# 2__Microcontroller.net
KiCad netlist of a schematic drawn in Altium Designer
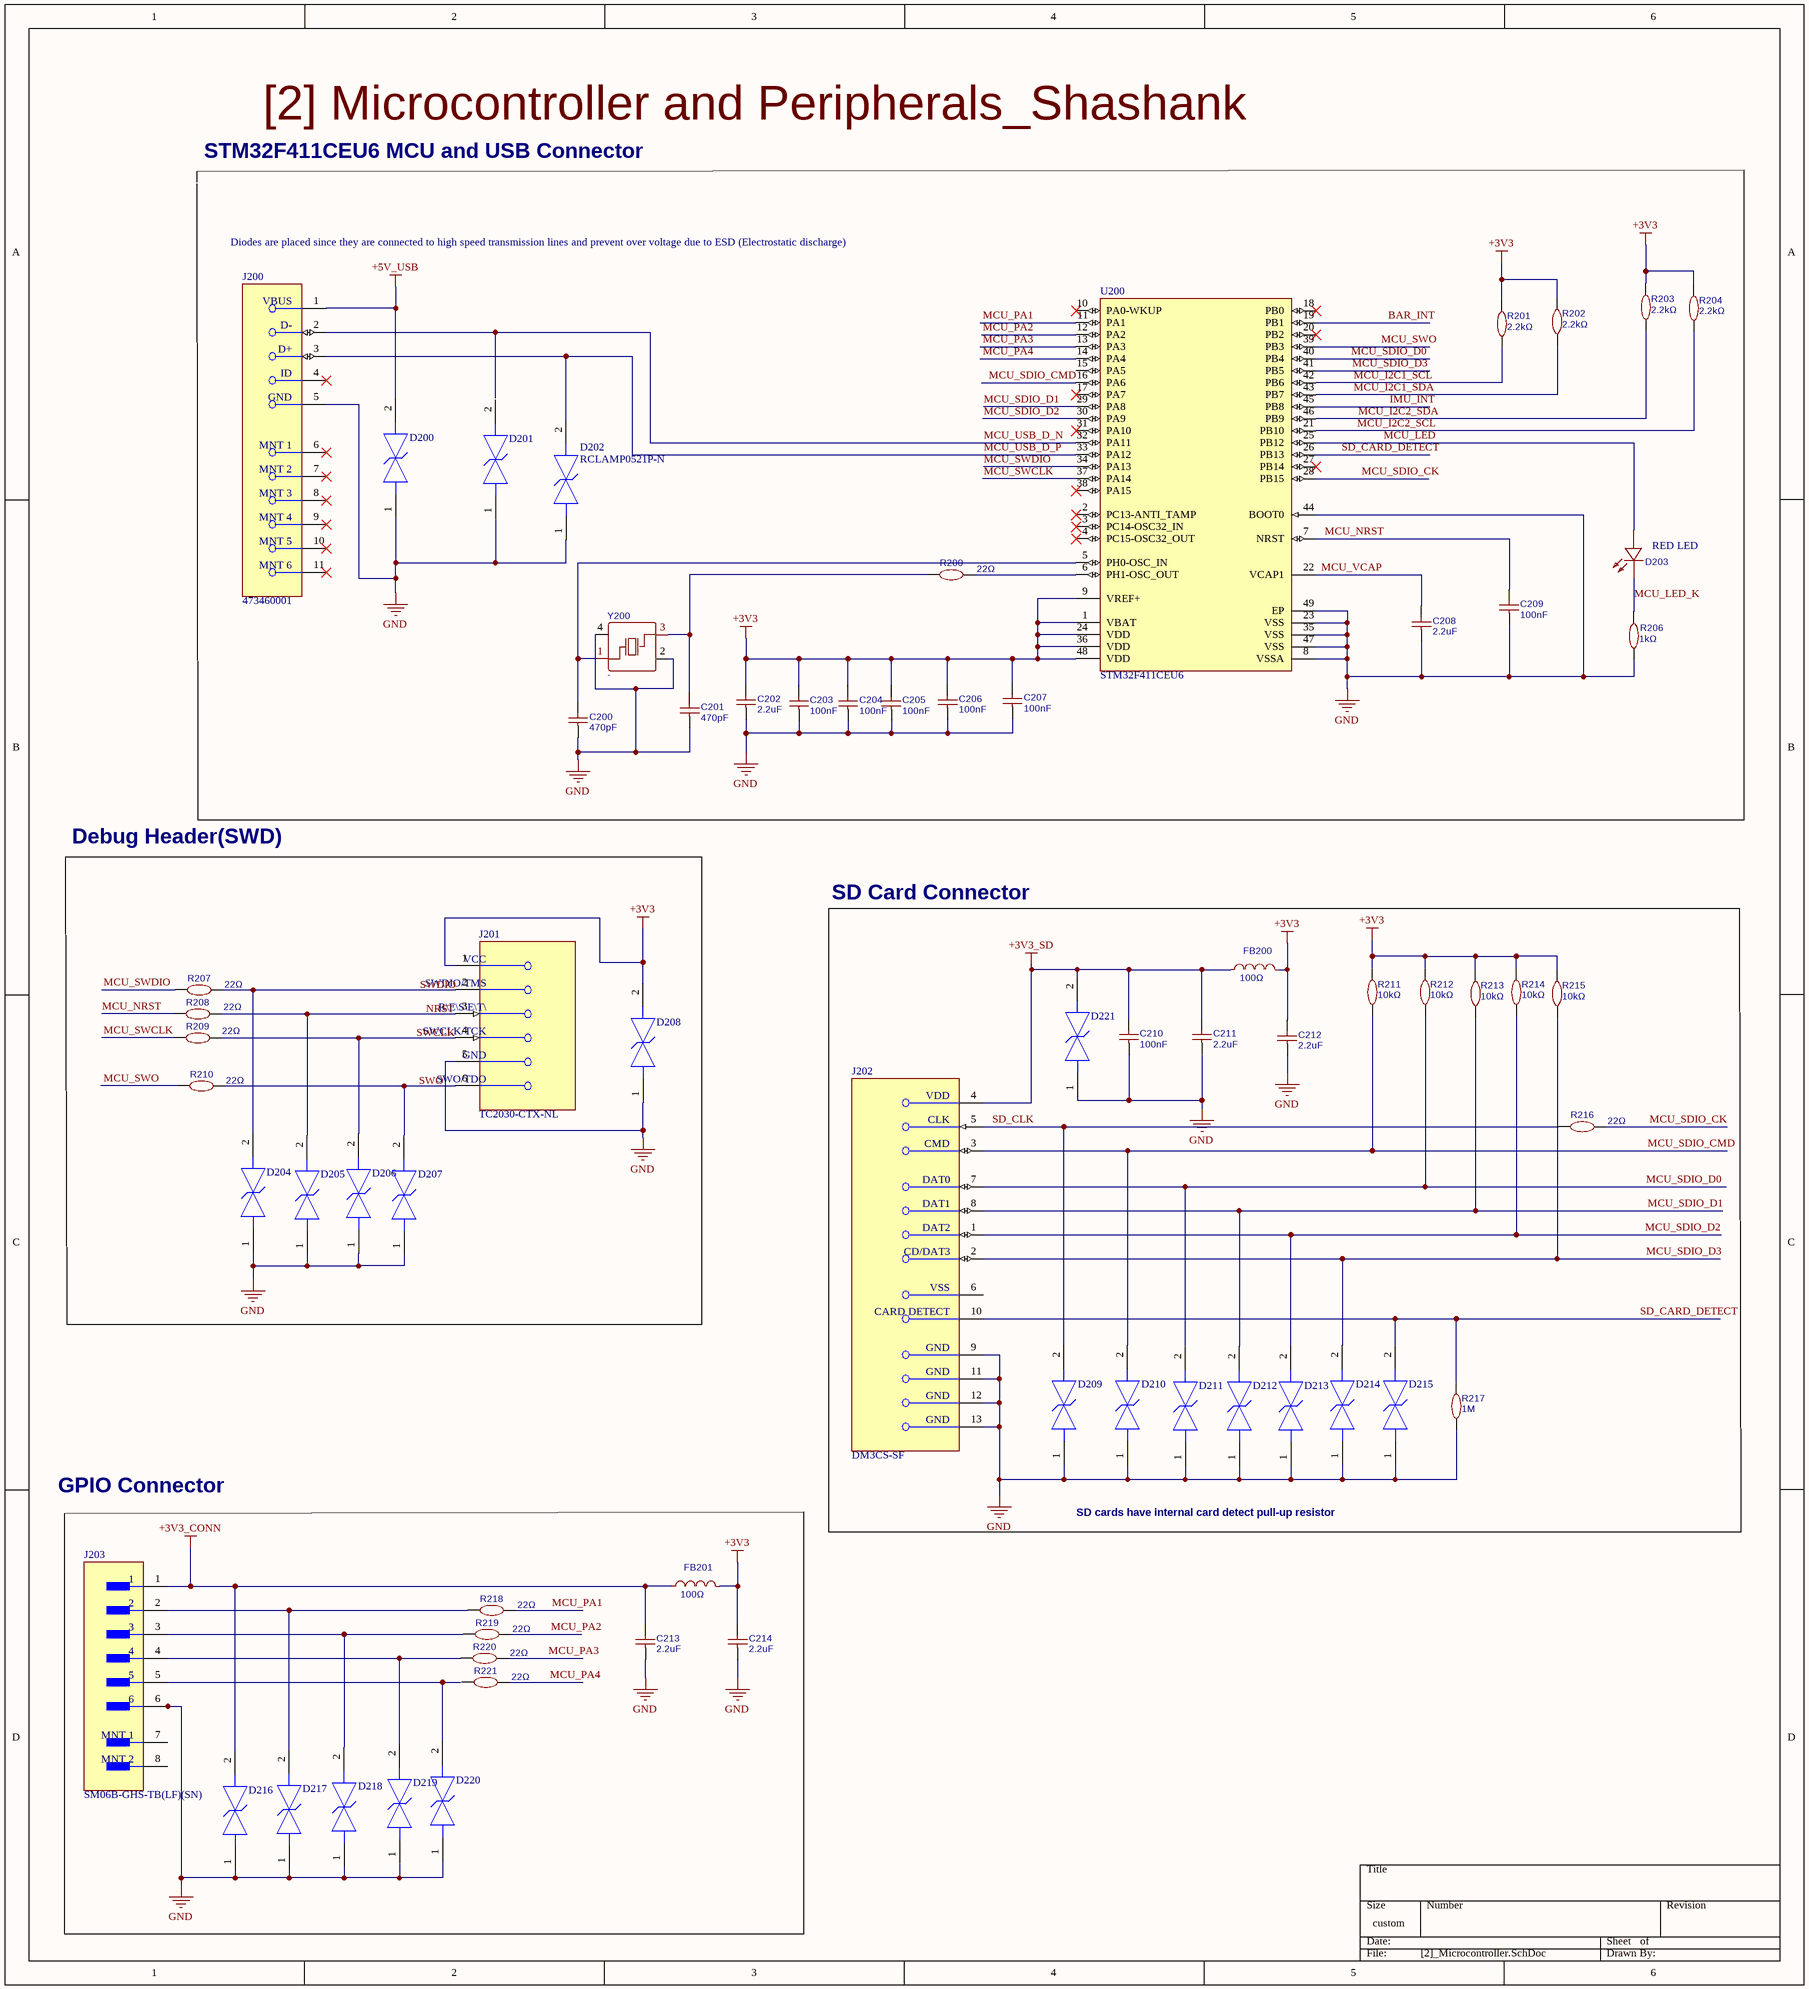
[diagram p0: [2]_Microcontroller.SchDoc]

(export (version "E")
  (design (tool "Eeschema 10.0.6"))
  (components
    (comp (ref "C200")
      (value "470pF")
      (footprint "C0402")
      (fields (field (name "MANUFACTURER") "FH(风华)") (field (name "MANUFACTURER PART") "0402B471K500NT"))
      (libsource (lib "Power_Lib") (part "470pF"))
    )
    (comp (ref "C201")
      (value "470pF")
      (footprint "C0402")
      (fields (field (name "MANUFACTURER") "FH(风华)") (field (name "MANUFACTURER PART") "0402B471K500NT"))
      (libsource (lib "Power_Lib") (part "470pF"))
    )
    (comp (ref "C202")
      (value "2.2uF")
      (footprint "C0603")
      (fields
        (field (name "MANUFACTURER PART") "CL10A225KO8NNNC")
        (field (name "MANUFACTURER") "SAMSUNG(三星)")
      )
      (libsource (lib "Power_Lib") (part "2.2uF"))
    )
    (comp (ref "C203")
      (value "100nF")
      (footprint "C0402")
      (fields (field (name "MANUFACTURER") "FH(风华)") (field (name "MANUFACTURER PART") "0402B471K500NT"))
      (libsource (lib "Power_Lib") (part "470pF"))
    )
    (comp (ref "C204")
      (value "100nF")
      (footprint "C0402")
      (fields (field (name "MANUFACTURER") "FH(风华)") (field (name "MANUFACTURER PART") "0402B471K500NT"))
      (libsource (lib "Power_Lib") (part "470pF"))
    )
    (comp (ref "C205")
      (value "100nF")
      (footprint "C0402")
      (fields (field (name "MANUFACTURER") "FH(风华)") (field (name "MANUFACTURER PART") "0402B471K500NT"))
      (libsource (lib "Power_Lib") (part "470pF"))
    )
    (comp (ref "C206")
      (value "100nF")
      (footprint "C0402")
      (fields (field (name "MANUFACTURER") "FH(风华)") (field (name "MANUFACTURER PART") "0402B471K500NT"))
      (libsource (lib "Power_Lib") (part "470pF"))
    )
    (comp (ref "C207")
      (value "100nF")
      (footprint "C0402")
      (fields (field (name "MANUFACTURER") "FH(风华)") (field (name "MANUFACTURER PART") "0402B471K500NT"))
      (libsource (lib "Power_Lib") (part "470pF"))
    )
    (comp (ref "C208")
      (value "2.2uF")
      (footprint "C0603")
      (fields
        (field (name "MANUFACTURER PART") "CL10A225KO8NNNC")
        (field (name "MANUFACTURER") "SAMSUNG(三星)")
      )
      (libsource (lib "Power_Lib") (part "2.2uF"))
    )
    (comp (ref "C209")
      (value "100nF")
      (footprint "C0402")
      (fields (field (name "MANUFACTURER") "FH(风华)") (field (name "MANUFACTURER PART") "0402B471K500NT"))
      (libsource (lib "Power_Lib") (part "470pF"))
    )
    (comp (ref "C210")
      (value "100nF")
      (footprint "C0402")
      (fields (field (name "MANUFACTURER") "FH(风华)") (field (name "MANUFACTURER PART") "0402B471K500NT"))
      (libsource (lib "Power_Lib") (part "470pF"))
    )
    (comp (ref "C211")
      (value "2.2uF")
      (footprint "C0603")
      (fields
        (field (name "MANUFACTURER PART") "CL10A225KO8NNNC")
        (field (name "MANUFACTURER") "SAMSUNG(三星)")
      )
      (libsource (lib "Power_Lib") (part "2.2uF"))
    )
    (comp (ref "C212")
      (value "2.2uF")
      (footprint "C0603")
      (fields
        (field (name "MANUFACTURER PART") "CL10A225KO8NNNC")
        (field (name "MANUFACTURER") "SAMSUNG(三星)")
      )
      (libsource (lib "Power_Lib") (part "2.2uF"))
    )
    (comp (ref "C213")
      (value "2.2uF")
      (footprint "C0603")
      (fields
        (field (name "MANUFACTURER PART") "CL10A225KO8NNNC")
        (field (name "MANUFACTURER") "SAMSUNG(三星)")
      )
      (libsource (lib "Power_Lib") (part "2.2uF"))
    )
    (comp (ref "C214")
      (value "2.2uF")
      (footprint "C0603")
      (fields
        (field (name "MANUFACTURER PART") "CL10A225KO8NNNC")
        (field (name "MANUFACTURER") "SAMSUNG(三星)")
      )
      (libsource (lib "Power_Lib") (part "2.2uF"))
    )
    (comp (ref "D200")
      (value "PESD0402-140")
      (footprint "FP-PESD0402-MFG")
      (description "TVS DIODE 14V 40V 0402")
      (fields
        (field (name "OCTOPART") "https://octopart.com/pesd0402-140-littelfuse-74215061")
        (field (name "MANUFACTURER") "Littelfuse Inc.")
      )
      (libsource (lib "Altium Content Vault") (part "edccc070dd5cba1f9372128faf3915e"))
    )
    (comp (ref "D201")
      (value "PESD0402-140")
      (footprint "FP-PESD0402-MFG")
      (description "TVS DIODE 14V 40V 0402")
      (fields
        (field (name "OCTOPART") "https://octopart.com/pesd0402-140-littelfuse-74215061")
        (field (name "MANUFACTURER") "Littelfuse Inc.")
      )
      (libsource (lib "Altium Content Vault") (part "edccc070dd5cba1f9372128faf3915e"))
    )
    (comp (ref "D202")
      (value "RCLAMP0521P-N")
      (footprint "FP-PESD0402-MFG")
      (description "TVS DIODE 14V 40V 0402")
      (fields
        (field (name "MANUFACTURER PART NUMBER") "PESD0402-140")
        (field (name "OCTOPART") "https://octopart.com/pesd0402-140-littelfuse-74215061")
      )
      (libsource (lib "Altium Content Vault") (part "edccc070dd5cba1f9372128faf3915e"))
    )
    (comp (ref "D203")
      (value "FC-F1005UGK-520M5")
      (footprint "LED0402-RD")
      (fields
        (field (name "MANUFACTURER") "国星光电")
        (field (name "MANUFACTURER PART") "NCD0402G1")
        (field (name "CONTRIBUTOR") "LCSC")
      )
      (libsource (lib "Power_Lib") (part "FC-F1005UGK-520M5"))
    )
    (comp (ref "D204")
      (value "PESD0402-140")
      (footprint "FP-PESD0402-MFG")
      (description "TVS DIODE 14V 40V 0402")
      (fields
        (field (name "OCTOPART") "https://octopart.com/pesd0402-140-littelfuse-74215061")
        (field (name "MANUFACTURER") "Littelfuse Inc.")
      )
      (libsource (lib "Altium Content Vault") (part "edccc070dd5cba1f9372128faf3915e"))
    )
    (comp (ref "D205")
      (value "PESD0402-140")
      (footprint "FP-PESD0402-MFG")
      (description "TVS DIODE 14V 40V 0402")
      (fields
        (field (name "OCTOPART") "https://octopart.com/pesd0402-140-littelfuse-74215061")
        (field (name "MANUFACTURER") "Littelfuse Inc.")
      )
      (libsource (lib "Altium Content Vault") (part "edccc070dd5cba1f9372128faf3915e"))
    )
    (comp (ref "D206")
      (value "PESD0402-140")
      (footprint "FP-PESD0402-MFG")
      (description "TVS DIODE 14V 40V 0402")
      (fields
        (field (name "OCTOPART") "https://octopart.com/pesd0402-140-littelfuse-74215061")
        (field (name "MANUFACTURER") "Littelfuse Inc.")
      )
      (libsource (lib "Altium Content Vault") (part "edccc070dd5cba1f9372128faf3915e"))
    )
    (comp (ref "D207")
      (value "PESD0402-140")
      (footprint "FP-PESD0402-MFG")
      (description "TVS DIODE 14V 40V 0402")
      (fields
        (field (name "OCTOPART") "https://octopart.com/pesd0402-140-littelfuse-74215061")
        (field (name "MANUFACTURER") "Littelfuse Inc.")
      )
      (libsource (lib "Altium Content Vault") (part "edccc070dd5cba1f9372128faf3915e"))
    )
    (comp (ref "D208")
      (value "PESD0402-140")
      (footprint "FP-PESD0402-MFG")
      (description "TVS DIODE 14V 40V 0402")
      (fields
        (field (name "OCTOPART") "https://octopart.com/pesd0402-140-littelfuse-74215061")
        (field (name "MANUFACTURER") "Littelfuse Inc.")
      )
      (libsource (lib "Altium Content Vault") (part "edccc070dd5cba1f9372128faf3915e"))
    )
    (comp (ref "D209")
      (value "PESD0402-140")
      (footprint "FP-PESD0402-MFG")
      (description "TVS DIODE 14V 40V 0402")
      (fields
        (field (name "OCTOPART") "https://octopart.com/pesd0402-140-littelfuse-74215061")
        (field (name "MANUFACTURER") "Littelfuse Inc.")
      )
      (libsource (lib "Altium Content Vault") (part "edccc070dd5cba1f9372128faf3915e"))
    )
    (comp (ref "D210")
      (value "PESD0402-140")
      (footprint "FP-PESD0402-MFG")
      (description "TVS DIODE 14V 40V 0402")
      (fields
        (field (name "OCTOPART") "https://octopart.com/pesd0402-140-littelfuse-74215061")
        (field (name "MANUFACTURER") "Littelfuse Inc.")
      )
      (libsource (lib "Altium Content Vault") (part "edccc070dd5cba1f9372128faf3915e"))
    )
    (comp (ref "D211")
      (value "PESD0402-140")
      (footprint "FP-PESD0402-MFG")
      (description "TVS DIODE 14V 40V 0402")
      (fields
        (field (name "OCTOPART") "https://octopart.com/pesd0402-140-littelfuse-74215061")
        (field (name "MANUFACTURER") "Littelfuse Inc.")
      )
      (libsource (lib "Altium Content Vault") (part "edccc070dd5cba1f9372128faf3915e"))
    )
    (comp (ref "D212")
      (value "PESD0402-140")
      (footprint "FP-PESD0402-MFG")
      (description "TVS DIODE 14V 40V 0402")
      (fields
        (field (name "OCTOPART") "https://octopart.com/pesd0402-140-littelfuse-74215061")
        (field (name "MANUFACTURER") "Littelfuse Inc.")
      )
      (libsource (lib "Altium Content Vault") (part "edccc070dd5cba1f9372128faf3915e"))
    )
    (comp (ref "D213")
      (value "PESD0402-140")
      (footprint "FP-PESD0402-MFG")
      (description "TVS DIODE 14V 40V 0402")
      (fields
        (field (name "OCTOPART") "https://octopart.com/pesd0402-140-littelfuse-74215061")
        (field (name "MANUFACTURER") "Littelfuse Inc.")
      )
      (libsource (lib "Altium Content Vault") (part "edccc070dd5cba1f9372128faf3915e"))
    )
    (comp (ref "D214")
      (value "PESD0402-140")
      (footprint "FP-PESD0402-MFG")
      (description "TVS DIODE 14V 40V 0402")
      (fields
        (field (name "OCTOPART") "https://octopart.com/pesd0402-140-littelfuse-74215061")
        (field (name "MANUFACTURER") "Littelfuse Inc.")
      )
      (libsource (lib "Altium Content Vault") (part "edccc070dd5cba1f9372128faf3915e"))
    )
    (comp (ref "D215")
      (value "PESD0402-140")
      (footprint "FP-PESD0402-MFG")
      (description "TVS DIODE 14V 40V 0402")
      (fields
        (field (name "OCTOPART") "https://octopart.com/pesd0402-140-littelfuse-74215061")
        (field (name "MANUFACTURER") "Littelfuse Inc.")
      )
      (libsource (lib "Altium Content Vault") (part "edccc070dd5cba1f9372128faf3915e"))
    )
    (comp (ref "D216")
      (value "PESD0402-140")
      (footprint "FP-PESD0402-MFG")
      (description "TVS DIODE 14V 40V 0402")
      (fields
        (field (name "OCTOPART") "https://octopart.com/pesd0402-140-littelfuse-74215061")
        (field (name "MANUFACTURER") "Littelfuse Inc.")
      )
      (libsource (lib "Altium Content Vault") (part "edccc070dd5cba1f9372128faf3915e"))
    )
    (comp (ref "D217")
      (value "PESD0402-140")
      (footprint "FP-PESD0402-MFG")
      (description "TVS DIODE 14V 40V 0402")
      (fields
        (field (name "OCTOPART") "https://octopart.com/pesd0402-140-littelfuse-74215061")
        (field (name "MANUFACTURER") "Littelfuse Inc.")
      )
      (libsource (lib "Altium Content Vault") (part "edccc070dd5cba1f9372128faf3915e"))
    )
    (comp (ref "D218")
      (value "PESD0402-140")
      (footprint "FP-PESD0402-MFG")
      (description "TVS DIODE 14V 40V 0402")
      (fields
        (field (name "OCTOPART") "https://octopart.com/pesd0402-140-littelfuse-74215061")
        (field (name "MANUFACTURER") "Littelfuse Inc.")
      )
      (libsource (lib "Altium Content Vault") (part "edccc070dd5cba1f9372128faf3915e"))
    )
    (comp (ref "D219")
      (value "PESD0402-140")
      (footprint "FP-PESD0402-MFG")
      (description "TVS DIODE 14V 40V 0402")
      (fields
        (field (name "OCTOPART") "https://octopart.com/pesd0402-140-littelfuse-74215061")
        (field (name "MANUFACTURER") "Littelfuse Inc.")
      )
      (libsource (lib "Altium Content Vault") (part "edccc070dd5cba1f9372128faf3915e"))
    )
    (comp (ref "D220")
      (value "PESD0402-140")
      (footprint "FP-PESD0402-MFG")
      (description "TVS DIODE 14V 40V 0402")
      (fields
        (field (name "OCTOPART") "https://octopart.com/pesd0402-140-littelfuse-74215061")
        (field (name "MANUFACTURER") "Littelfuse Inc.")
      )
      (libsource (lib "Altium Content Vault") (part "edccc070dd5cba1f9372128faf3915e"))
    )
    (comp (ref "D221")
      (value "PESD0402-140")
      (footprint "FP-PESD0402-MFG")
      (description "TVS DIODE 14V 40V 0402")
      (fields
        (field (name "OCTOPART") "https://octopart.com/pesd0402-140-littelfuse-74215061")
        (field (name "MANUFACTURER") "Littelfuse Inc.")
      )
      (libsource (lib "Altium Content Vault") (part "edccc070dd5cba1f9372128faf3915e"))
    )
    (comp (ref "FB200")
      (value "100Ω")
      (footprint "L0603")
      (fields
        (field (name "MANUFACTURER") "Sunlord(顺络)")
        (field (name "MANUFACTURER PART") "PZ1608D121-2R0TF")
      )
      (libsource (lib "Power_Lib") (part "120Ω"))
    )
    (comp (ref "FB201")
      (value "100Ω")
      (footprint "L0603")
      (fields
        (field (name "MANUFACTURER") "Sunlord(顺络)")
        (field (name "MANUFACTURER PART") "PZ1608D121-2R0TF")
      )
      (libsource (lib "Power_Lib") (part "120Ω"))
    )
    (comp (ref "J200")
      (value "473460001")
      (footprint "FP-473460001-MFG")
      (description "CONN RCPT USB2.0 MICRO B SMD R/A")
      (fields
        (field (name "OCTOPART") "https://octopart.com/47346-0001-molex-7164928")
        (field (name "MANUFACTURER") "Molex")
      )
      (libsource (lib "Altium Content Vault") (part "53ae1f1d9b557310b43ca686e5bb76a"))
    )
    (comp (ref "J201")
      (value "TC2030-CTX-NL")
      (footprint "FP-TC2030-CTX-NL-MFG")
      (description "6-Pin “No legs” TC2030 Plug-of-Nails™ Cable for use with ARM Cortex processors")
      (libsource (lib "Altium Content Vault") (part "e3fe093a55dc37473f431e03719485e"))
    )
    (comp (ref "J202")
      (value "DM3CS-SF")
      (footprint "FP-DM3CS-SF-MFG")
      (description "CONN MICRO SD CARD HINGED TYPE")
      (libsource (lib "Altium Content Vault") (part "bac915de5305cfdd1ca301aae530106"))
    )
    (comp (ref "J203")
      (value "SM06B-GHS-TB(LF)(SN)")
      (footprint "FP-SM06B-GHS-TB_LF_SN-MFG")
      (description "CONN HEADER SMD R/A 6POS 1.25MM")
      (libsource (lib "Altium Content Vault") (part "ed24c53d9ba001d1a2a686240a95171"))
    )
    (comp (ref "R200")
      (value "22Ω")
      (footprint "R0402")
      (fields
        (field (name "MANUFACTURER") "UNI-ROYAL(厚声)")
        (field (name "MANUFACTURER PART") "0402WGF1001TCE")
      )
      (libsource (lib "Power_Lib") (part "1kΩ"))
    )
    (comp (ref "R201")
      (value "2.2kΩ")
      (footprint "R0402")
      (fields
        (field (name "MANUFACTURER") "UNI-ROYAL(厚声)")
        (field (name "MANUFACTURER PART") "0402WGF1001TCE")
      )
      (libsource (lib "Power_Lib") (part "1kΩ"))
    )
    (comp (ref "R202")
      (value "2.2kΩ")
      (footprint "R0402")
      (fields
        (field (name "MANUFACTURER") "UNI-ROYAL(厚声)")
        (field (name "MANUFACTURER PART") "0402WGF1001TCE")
      )
      (libsource (lib "Power_Lib") (part "1kΩ"))
    )
    (comp (ref "R203")
      (value "2.2kΩ")
      (footprint "R0402")
      (fields
        (field (name "MANUFACTURER") "UNI-ROYAL(厚声)")
        (field (name "MANUFACTURER PART") "0402WGF1001TCE")
      )
      (libsource (lib "Power_Lib") (part "1kΩ"))
    )
    (comp (ref "R204")
      (value "2.2kΩ")
      (footprint "R0402")
      (fields
        (field (name "MANUFACTURER") "UNI-ROYAL(厚声)")
        (field (name "MANUFACTURER PART") "0402WGF1001TCE")
      )
      (libsource (lib "Power_Lib") (part "1kΩ"))
    )
    (comp (ref "R206")
      (value "1kΩ")
      (footprint "R0402")
      (fields
        (field (name "MANUFACTURER") "UNI-ROYAL(厚声)")
        (field (name "MANUFACTURER PART") "0402WGF1001TCE")
      )
      (libsource (lib "Power_Lib") (part "1kΩ"))
    )
    (comp (ref "R207")
      (value "22Ω")
      (footprint "R0402")
      (fields
        (field (name "MANUFACTURER") "UNI-ROYAL(厚声)")
        (field (name "MANUFACTURER PART") "0402WGF1001TCE")
      )
      (libsource (lib "Power_Lib") (part "1kΩ"))
    )
    (comp (ref "R208")
      (value "22Ω")
      (footprint "R0402")
      (fields
        (field (name "MANUFACTURER") "UNI-ROYAL(厚声)")
        (field (name "MANUFACTURER PART") "0402WGF1001TCE")
      )
      (libsource (lib "Power_Lib") (part "1kΩ"))
    )
    (comp (ref "R209")
      (value "22Ω")
      (footprint "R0402")
      (fields
        (field (name "MANUFACTURER") "UNI-ROYAL(厚声)")
        (field (name "MANUFACTURER PART") "0402WGF1001TCE")
      )
      (libsource (lib "Power_Lib") (part "1kΩ"))
    )
    (comp (ref "R210")
      (value "22Ω")
      (footprint "R0402")
      (fields
        (field (name "MANUFACTURER") "UNI-ROYAL(厚声)")
        (field (name "MANUFACTURER PART") "0402WGF1001TCE")
      )
      (libsource (lib "Power_Lib") (part "1kΩ"))
    )
    (comp (ref "R211")
      (value "10kΩ")
      (footprint "R0402")
      (fields
        (field (name "MANUFACTURER") "UNI-ROYAL(厚声)")
        (field (name "MANUFACTURER PART") "0402WGF1001TCE")
      )
      (libsource (lib "Power_Lib") (part "1kΩ"))
    )
    (comp (ref "R212")
      (value "10kΩ")
      (footprint "R0402")
      (fields
        (field (name "MANUFACTURER") "UNI-ROYAL(厚声)")
        (field (name "MANUFACTURER PART") "0402WGF1001TCE")
      )
      (libsource (lib "Power_Lib") (part "1kΩ"))
    )
    (comp (ref "R213")
      (value "10kΩ")
      (footprint "R0402")
      (fields
        (field (name "MANUFACTURER") "UNI-ROYAL(厚声)")
        (field (name "MANUFACTURER PART") "0402WGF1001TCE")
      )
      (libsource (lib "Power_Lib") (part "1kΩ"))
    )
    (comp (ref "R214")
      (value "10kΩ")
      (footprint "R0402")
      (fields
        (field (name "MANUFACTURER") "UNI-ROYAL(厚声)")
        (field (name "MANUFACTURER PART") "0402WGF1001TCE")
      )
      (libsource (lib "Power_Lib") (part "1kΩ"))
    )
    (comp (ref "R215")
      (value "10kΩ")
      (footprint "R0402")
      (fields
        (field (name "MANUFACTURER") "UNI-ROYAL(厚声)")
        (field (name "MANUFACTURER PART") "0402WGF1001TCE")
      )
      (libsource (lib "Power_Lib") (part "1kΩ"))
    )
    (comp (ref "R216")
      (value "22Ω")
      (footprint "R0402")
      (fields
        (field (name "MANUFACTURER") "UNI-ROYAL(厚声)")
        (field (name "MANUFACTURER PART") "0402WGF1001TCE")
      )
      (libsource (lib "Power_Lib") (part "1kΩ"))
    )
    (comp (ref "R217")
      (value "1M")
      (footprint "R0402")
      (fields
        (field (name "MANUFACTURER") "UNI-ROYAL(厚声)")
        (field (name "MANUFACTURER PART") "0402WGF1001TCE")
      )
      (libsource (lib "Power_Lib") (part "1kΩ"))
    )
    (comp (ref "R218")
      (value "22Ω")
      (footprint "R0402")
      (fields
        (field (name "MANUFACTURER") "UNI-ROYAL(厚声)")
        (field (name "MANUFACTURER PART") "0402WGF1001TCE")
      )
      (libsource (lib "Power_Lib") (part "1kΩ"))
    )
    (comp (ref "R219")
      (value "22Ω")
      (footprint "R0402")
      (fields
        (field (name "MANUFACTURER") "UNI-ROYAL(厚声)")
        (field (name "MANUFACTURER PART") "0402WGF1001TCE")
      )
      (libsource (lib "Power_Lib") (part "1kΩ"))
    )
    (comp (ref "R220")
      (value "22Ω")
      (footprint "R0402")
      (fields
        (field (name "MANUFACTURER") "UNI-ROYAL(厚声)")
        (field (name "MANUFACTURER PART") "0402WGF1001TCE")
      )
      (libsource (lib "Power_Lib") (part "1kΩ"))
    )
    (comp (ref "R221")
      (value "22Ω")
      (footprint "R0402")
      (fields
        (field (name "MANUFACTURER") "UNI-ROYAL(厚声)")
        (field (name "MANUFACTURER PART") "0402WGF1001TCE")
      )
      (libsource (lib "Power_Lib") (part "1kΩ"))
    )
    (comp (ref "U200")
      (value "STM32F411CEU6")
      (footprint "STM-UFQFPN48_L")
      (libsource (lib "Altium Content Vault") (part "MC-ARM-STM32F411-UFQFPN48"))
    )
    (comp (ref "Y200")
      (value "-")
      (footprint "OSC-SMD_4P-L3.2-W2.5-BL")
      (fields
        (field (name "MANUFACTURER") "HELE(台湾加高)")
        (field (name "MANUFACTURER PART") "X3Z016000B91H-U")
        (field (name "CONTRIBUTOR") "LCSC")
      )
      (libsource (lib "Power_Lib") (part "Cystal Osc"))
    )
  )
  (nets
    (net (code "1") (name "+3V3") (class "Default")
      (node (ref "C202") (pin "2") (pinfunction "2_2") (pintype "passive"))
      (node (ref "C203") (pin "2") (pinfunction "2_2") (pintype "passive"))
      (node (ref "C204") (pin "2") (pinfunction "2_2") (pintype "passive"))
      (node (ref "C205") (pin "2") (pinfunction "2_2") (pintype "passive"))
      (node (ref "C206") (pin "2") (pinfunction "2_2") (pintype "passive"))
      (node (ref "C207") (pin "2") (pinfunction "2_2") (pintype "passive"))
      (node (ref "C212") (pin "2") (pinfunction "2_2") (pintype "passive"))
      (node (ref "C214") (pin "2") (pinfunction "2_2") (pintype "passive"))
      (node (ref "D208") (pin "2") (pinfunction "2_2") (pintype "passive"))
      (node (ref "FB200") (pin "2") (pinfunction "2_2") (pintype "passive"))
      (node (ref "FB201") (pin "2") (pinfunction "2_2") (pintype "passive"))
      (node (ref "J201") (pin "1") (pinfunction "VCC_1") (pintype "power_in"))
      (node (ref "R201") (pin "2") (pinfunction "2_2") (pintype "passive"))
      (node (ref "R202") (pin "2") (pinfunction "2_2") (pintype "passive"))
      (node (ref "R203") (pin "2") (pinfunction "2_2") (pintype "passive"))
      (node (ref "R204") (pin "2") (pinfunction "2_2") (pintype "passive"))
      (node (ref "R211") (pin "2") (pinfunction "2_2") (pintype "passive"))
      (node (ref "R212") (pin "2") (pinfunction "2_2") (pintype "passive"))
      (node (ref "R213") (pin "2") (pinfunction "2_2") (pintype "passive"))
      (node (ref "R214") (pin "2") (pinfunction "2_2") (pintype "passive"))
      (node (ref "R215") (pin "2") (pinfunction "2_2") (pintype "passive"))
      (node (ref "U200") (pin "1") (pinfunction "VBAT_1") (pintype "power_in"))
      (node (ref "U200") (pin "24") (pinfunction "VDD_24") (pintype "power_in"))
      (node (ref "U200") (pin "36") (pinfunction "VDD_36") (pintype "power_in"))
      (node (ref "U200") (pin "48") (pinfunction "VDD_48") (pintype "power_in"))
      (node (ref "U200") (pin "9") (pinfunction "VREF+_9") (pintype "power_in"))
    )
    (net (code "2") (name "+3V3_CONN") (class "Default")
      (node (ref "C213") (pin "2") (pinfunction "2_2") (pintype "passive"))
      (node (ref "D216") (pin "2") (pinfunction "2_2") (pintype "passive"))
      (node (ref "FB201") (pin "1") (pinfunction "1_1") (pintype "passive"))
      (node (ref "J203") (pin "1") (pinfunction "1_1") (pintype "passive"))
    )
    (net (code "3") (name "+3V3_SD") (class "Default")
      (node (ref "C210") (pin "2") (pinfunction "2_2") (pintype "passive"))
      (node (ref "C211") (pin "2") (pinfunction "2_2") (pintype "passive"))
      (node (ref "D221") (pin "2") (pinfunction "2_2") (pintype "passive"))
      (node (ref "FB200") (pin "1") (pinfunction "1_1") (pintype "passive"))
      (node (ref "J202") (pin "4") (pinfunction "VDD_4") (pintype "power_in"))
    )
    (net (code "4") (name "+5V_USB") (class "Default")
      (node (ref "D200") (pin "2") (pinfunction "2_2") (pintype "passive"))
      (node (ref "J200") (pin "1") (pinfunction "VBUS_1") (pintype "power_in"))
    )
    (net (code "5") (name "/BAR_INT") (class "Default")
      (node (ref "U200") (pin "19") (pinfunction "PB1_19") (pintype "bidirectional"))
    )
    (net (code "6") (name "/IMU_INT") (class "Default")
      (node (ref "U200") (pin "45") (pinfunction "PB8_45") (pintype "bidirectional"))
    )
    (net (code "7") (name "/MCU_I2C1_SCL") (class "Default")
      (node (ref "R201") (pin "1") (pinfunction "1_1") (pintype "passive"))
      (node (ref "U200") (pin "42") (pinfunction "PB6_42") (pintype "bidirectional"))
    )
    (net (code "8") (name "/MCU_I2C1_SDA") (class "Default")
      (node (ref "R202") (pin "1") (pinfunction "1_1") (pintype "passive"))
      (node (ref "U200") (pin "43") (pinfunction "PB7_43") (pintype "bidirectional"))
    )
    (net (code "9") (name "/MCU_I2C2_SCL") (class "Default")
      (node (ref "R204") (pin "1") (pinfunction "1_1") (pintype "passive"))
      (node (ref "U200") (pin "21") (pinfunction "PB10_21") (pintype "bidirectional"))
    )
    (net (code "10") (name "/MCU_I2C2_SDA") (class "Default")
      (node (ref "R203") (pin "1") (pinfunction "1_1") (pintype "passive"))
      (node (ref "U200") (pin "46") (pinfunction "PB9_46") (pintype "bidirectional"))
    )
    (net (code "11") (name "/MCU_LED") (class "Default")
      (node (ref "D203") (pin "2") (pinfunction "A_2") (pintype "passive"))
      (node (ref "U200") (pin "25") (pinfunction "PB12_25") (pintype "bidirectional"))
    )
    (net (code "12") (name "/MCU_LED_K") (class "Default")
      (node (ref "D203") (pin "1") (pinfunction "K_1") (pintype "passive"))
      (node (ref "R206") (pin "2") (pinfunction "2_2") (pintype "passive"))
    )
    (net (code "13") (name "/MCU_NRST") (class "Default")
      (node (ref "C209") (pin "2") (pinfunction "2_2") (pintype "passive"))
      (node (ref "R208") (pin "1") (pinfunction "1_1") (pintype "passive"))
      (node (ref "U200") (pin "7") (pinfunction "NRST_7") (pintype "bidirectional"))
    )
    (net (code "14") (name "/MCU_PA1") (class "Default")
      (node (ref "R218") (pin "2") (pinfunction "2_2") (pintype "passive"))
      (node (ref "U200") (pin "11") (pinfunction "PA1_11") (pintype "bidirectional"))
    )
    (net (code "15") (name "/MCU_PA2") (class "Default")
      (node (ref "R219") (pin "2") (pinfunction "2_2") (pintype "passive"))
      (node (ref "U200") (pin "12") (pinfunction "PA2_12") (pintype "bidirectional"))
    )
    (net (code "16") (name "/MCU_PA3") (class "Default")
      (node (ref "R220") (pin "2") (pinfunction "2_2") (pintype "passive"))
      (node (ref "U200") (pin "13") (pinfunction "PA3_13") (pintype "bidirectional"))
    )
    (net (code "17") (name "/MCU_PA4") (class "Default")
      (node (ref "R221") (pin "2") (pinfunction "2_2") (pintype "passive"))
      (node (ref "U200") (pin "14") (pinfunction "PA4_14") (pintype "bidirectional"))
    )
    (net (code "18") (name "/MCU_SDIO_CK") (class "Default")
      (node (ref "R216") (pin "2") (pinfunction "2_2") (pintype "passive"))
      (node (ref "U200") (pin "28") (pinfunction "PB15_28") (pintype "bidirectional"))
    )
    (net (code "19") (name "/MCU_SDIO_CMD") (class "Default")
      (node (ref "D210") (pin "2") (pinfunction "2_2") (pintype "passive"))
      (node (ref "J202") (pin "3") (pinfunction "CMD_3") (pintype "bidirectional"))
      (node (ref "R211") (pin "1") (pinfunction "1_1") (pintype "passive"))
      (node (ref "U200") (pin "16") (pinfunction "PA6_16") (pintype "bidirectional"))
    )
    (net (code "20") (name "/MCU_SDIO_D0") (class "Default")
      (node (ref "D211") (pin "2") (pinfunction "2_2") (pintype "passive"))
      (node (ref "J202") (pin "7") (pinfunction "DAT0_7") (pintype "bidirectional"))
      (node (ref "R212") (pin "1") (pinfunction "1_1") (pintype "passive"))
      (node (ref "U200") (pin "40") (pinfunction "PB4_40") (pintype "bidirectional"))
    )
    (net (code "21") (name "/MCU_SDIO_D1") (class "Default")
      (node (ref "D212") (pin "2") (pinfunction "2_2") (pintype "passive"))
      (node (ref "J202") (pin "8") (pinfunction "DAT1_8") (pintype "bidirectional"))
      (node (ref "R213") (pin "1") (pinfunction "1_1") (pintype "passive"))
      (node (ref "U200") (pin "29") (pinfunction "PA8_29") (pintype "bidirectional"))
    )
    (net (code "22") (name "/MCU_SDIO_D2") (class "Default")
      (node (ref "D213") (pin "2") (pinfunction "2_2") (pintype "passive"))
      (node (ref "J202") (pin "1") (pinfunction "DAT2_1") (pintype "bidirectional"))
      (node (ref "R214") (pin "1") (pinfunction "1_1") (pintype "passive"))
      (node (ref "U200") (pin "30") (pinfunction "PA9_30") (pintype "bidirectional"))
    )
    (net (code "23") (name "/MCU_SDIO_D3") (class "Default")
      (node (ref "D214") (pin "2") (pinfunction "2_2") (pintype "passive"))
      (node (ref "J202") (pin "2") (pinfunction "CD/DAT3_2") (pintype "bidirectional"))
      (node (ref "R215") (pin "1") (pinfunction "1_1") (pintype "passive"))
      (node (ref "U200") (pin "41") (pinfunction "PB5_41") (pintype "bidirectional"))
    )
    (net (code "24") (name "/MCU_SWCLK") (class "Default")
      (node (ref "R209") (pin "1") (pinfunction "1_1") (pintype "passive"))
      (node (ref "U200") (pin "37") (pinfunction "PA14_37") (pintype "bidirectional"))
    )
    (net (code "25") (name "/MCU_SWDIO") (class "Default")
      (node (ref "R207") (pin "1") (pinfunction "1_1") (pintype "passive"))
      (node (ref "U200") (pin "34") (pinfunction "PA13_34") (pintype "bidirectional"))
    )
    (net (code "26") (name "/MCU_SWO") (class "Default")
      (node (ref "R210") (pin "1") (pinfunction "1_1") (pintype "passive"))
      (node (ref "U200") (pin "39") (pinfunction "PB3_39") (pintype "bidirectional"))
    )
    (net (code "27") (name "/MCU_USB_D_N") (class "Default")
      (node (ref "J200") (pin "2") (pinfunction "D-_2") (pintype "bidirectional"))
      (node (ref "U200") (pin "32") (pinfunction "PA11_32") (pintype "bidirectional"))
    )
    (net (code "28") (name "/MCU_USB_D_P") (class "Default")
      (node (ref "D202") (pin "2") (pinfunction "2_2") (pintype "passive"))
      (node (ref "J200") (pin "3") (pinfunction "D+_3") (pintype "bidirectional"))
      (node (ref "U200") (pin "33") (pinfunction "PA12_33") (pintype "bidirectional"))
    )
    (net (code "29") (name "/MCU_VCAP") (class "Default")
      (node (ref "C208") (pin "2") (pinfunction "2_2") (pintype "passive"))
      (node (ref "U200") (pin "22") (pinfunction "VCAP1_22") (pintype "passive"))
    )
    (net (code "31") (name "/SD_CARD_DETECT") (class "Default")
      (node (ref "D215") (pin "2") (pinfunction "2_2") (pintype "passive"))
      (node (ref "J202") (pin "10") (pinfunction "CARD_DETECT_10") (pintype "passive"))
      (node (ref "R217") (pin "2") (pinfunction "2_2") (pintype "passive"))
      (node (ref "U200") (pin "26") (pinfunction "PB13_26") (pintype "bidirectional"))
    )
    (net (code "32") (name "/SD_CLK") (class "Default")
      (node (ref "D209") (pin "2") (pinfunction "2_2") (pintype "passive"))
      (node (ref "J202") (pin "5") (pinfunction "CLK_5") (pintype "input"))
      (node (ref "R216") (pin "1") (pinfunction "1_1") (pintype "passive"))
    )
    (net (code "36") (name "GND") (class "Default")
      (node (ref "C200") (pin "1") (pinfunction "1_1") (pintype "passive"))
      (node (ref "C201") (pin "1") (pinfunction "1_1") (pintype "passive"))
      (node (ref "C202") (pin "1") (pinfunction "1_1") (pintype "passive"))
      (node (ref "C203") (pin "1") (pinfunction "1_1") (pintype "passive"))
      (node (ref "C204") (pin "1") (pinfunction "1_1") (pintype "passive"))
      (node (ref "C205") (pin "1") (pinfunction "1_1") (pintype "passive"))
      (node (ref "C206") (pin "1") (pinfunction "1_1") (pintype "passive"))
      (node (ref "C207") (pin "1") (pinfunction "1_1") (pintype "passive"))
      (node (ref "C208") (pin "1") (pinfunction "1_1") (pintype "passive"))
      (node (ref "C209") (pin "1") (pinfunction "1_1") (pintype "passive"))
      (node (ref "C210") (pin "1") (pinfunction "1_1") (pintype "passive"))
      (node (ref "C211") (pin "1") (pinfunction "1_1") (pintype "passive"))
      (node (ref "C212") (pin "1") (pinfunction "1_1") (pintype "passive"))
      (node (ref "C213") (pin "1") (pinfunction "1_1") (pintype "passive"))
      (node (ref "C214") (pin "1") (pinfunction "1_1") (pintype "passive"))
      (node (ref "D200") (pin "1") (pinfunction "1_1") (pintype "passive"))
      (node (ref "D201") (pin "1") (pinfunction "1_1") (pintype "passive"))
      (node (ref "D202") (pin "1") (pinfunction "1_1") (pintype "passive"))
      (node (ref "D204") (pin "1") (pinfunction "1_1") (pintype "passive"))
      (node (ref "D205") (pin "1") (pinfunction "1_1") (pintype "passive"))
      (node (ref "D206") (pin "1") (pinfunction "1_1") (pintype "passive"))
      (node (ref "D207") (pin "1") (pinfunction "1_1") (pintype "passive"))
      (node (ref "D208") (pin "1") (pinfunction "1_1") (pintype "passive"))
      (node (ref "D209") (pin "1") (pinfunction "1_1") (pintype "passive"))
      (node (ref "D210") (pin "1") (pinfunction "1_1") (pintype "passive"))
      (node (ref "D211") (pin "1") (pinfunction "1_1") (pintype "passive"))
      (node (ref "D212") (pin "1") (pinfunction "1_1") (pintype "passive"))
      (node (ref "D213") (pin "1") (pinfunction "1_1") (pintype "passive"))
      (node (ref "D214") (pin "1") (pinfunction "1_1") (pintype "passive"))
      (node (ref "D215") (pin "1") (pinfunction "1_1") (pintype "passive"))
      (node (ref "D216") (pin "1") (pinfunction "1_1") (pintype "passive"))
      (node (ref "D217") (pin "1") (pinfunction "1_1") (pintype "passive"))
      (node (ref "D218") (pin "1") (pinfunction "1_1") (pintype "passive"))
      (node (ref "D219") (pin "1") (pinfunction "1_1") (pintype "passive"))
      (node (ref "D220") (pin "1") (pinfunction "1_1") (pintype "passive"))
      (node (ref "D221") (pin "1") (pinfunction "1_1") (pintype "passive"))
      (node (ref "J200") (pin "5") (pinfunction "GND_5") (pintype "power_in"))
      (node (ref "J201") (pin "5") (pinfunction "GND_5") (pintype "power_in"))
      (node (ref "J202") (pin "11") (pinfunction "GND_11") (pintype "power_in"))
      (node (ref "J202") (pin "12") (pinfunction "GND_12") (pintype "power_in"))
      (node (ref "J202") (pin "13") (pinfunction "GND_13") (pintype "power_in"))
      (node (ref "J202") (pin "9") (pinfunction "GND_9") (pintype "power_in"))
      (node (ref "J203") (pin "6") (pinfunction "6_6") (pintype "passive"))
      (node (ref "R206") (pin "1") (pinfunction "1_1") (pintype "passive"))
      (node (ref "R217") (pin "1") (pinfunction "1_1") (pintype "passive"))
      (node (ref "U200") (pin "23") (pinfunction "VSS_23") (pintype "power_in"))
      (node (ref "U200") (pin "35") (pinfunction "VSS_35") (pintype "power_in"))
      (node (ref "U200") (pin "44") (pinfunction "BOOT0_44") (pintype "input"))
      (node (ref "U200") (pin "47") (pinfunction "VSS_47") (pintype "power_in"))
      (node (ref "U200") (pin "49") (pinfunction "EP_49") (pintype "power_in"))
      (node (ref "U200") (pin "8") (pinfunction "VSSA_8") (pintype "power_in"))
      (node (ref "Y200") (pin "2") (pinfunction "GND_2") (pintype "passive"))
      (node (ref "Y200") (pin "4") (pinfunction "GND_4") (pintype "passive"))
    )
    (net (code "37") (name "Net-(D217-Pad2)") (class "Default")
      (node (ref "D217") (pin "2") (pinfunction "2_2") (pintype "passive"))
      (node (ref "J203") (pin "2") (pinfunction "2_2") (pintype "passive"))
      (node (ref "R218") (pin "1") (pinfunction "1_1") (pintype "passive"))
    )
    (net (code "38") (name "Net-(D218-Pad2)") (class "Default")
      (node (ref "D218") (pin "2") (pinfunction "2_2") (pintype "passive"))
      (node (ref "J203") (pin "3") (pinfunction "3_3") (pintype "passive"))
      (node (ref "R219") (pin "1") (pinfunction "1_1") (pintype "passive"))
    )
    (net (code "39") (name "Net-(D219-Pad2)") (class "Default")
      (node (ref "D219") (pin "2") (pinfunction "2_2") (pintype "passive"))
      (node (ref "J203") (pin "4") (pinfunction "4_4") (pintype "passive"))
      (node (ref "R220") (pin "1") (pinfunction "1_1") (pintype "passive"))
    )
    (net (code "40") (name "Net-(D220-Pad2)") (class "Default")
      (node (ref "D220") (pin "2") (pinfunction "2_2") (pintype "passive"))
      (node (ref "J203") (pin "5") (pinfunction "5_5") (pintype "passive"))
    )
    (net (code "41") (name "Net-(J201-SWCLK{slash}TCK)") (class "Default")
      (node (ref "D206") (pin "2") (pinfunction "2_2") (pintype "passive"))
      (node (ref "J201") (pin "4") (pinfunction "SWCLK/TCK_4") (pintype "input"))
      (node (ref "R209") (pin "2") (pinfunction "2_2") (pintype "passive"))
    )
    (net (code "42") (name "Net-(J201-SWDIO{slash}TMS)") (class "Default")
      (node (ref "D204") (pin "2") (pinfunction "2_2") (pintype "passive"))
      (node (ref "J201") (pin "2") (pinfunction "SWDIO/TMS_2") (pintype "passive"))
      (node (ref "R207") (pin "2") (pinfunction "2_2") (pintype "passive"))
    )
    (net (code "43") (name "Net-(J201-SWO{slash}TDO)") (class "Default")
      (node (ref "D207") (pin "2") (pinfunction "2_2") (pintype "passive"))
      (node (ref "J201") (pin "6") (pinfunction "SWO/TDO_6") (pintype "passive"))
      (node (ref "R210") (pin "2") (pinfunction "2_2") (pintype "passive"))
    )
    (net (code "44") (name "Net-(J201-~{RESET})") (class "Default")
      (node (ref "D205") (pin "2") (pinfunction "2_2") (pintype "passive"))
      (node (ref "J201") (pin "3") (pinfunction "~{RESET}_3") (pintype "input"))
      (node (ref "R208") (pin "2") (pinfunction "2_2") (pintype "passive"))
    )
    (net (code "45") (name "Net-(U200-PH0-OSC_IN)") (class "Default")
      (node (ref "C200") (pin "2") (pinfunction "2_2") (pintype "passive"))
      (node (ref "U200") (pin "5") (pinfunction "PH0-OSC_IN_5") (pintype "bidirectional"))
      (node (ref "Y200") (pin "1") (pinfunction "OSC1_1") (pintype "passive"))
    )
    (net (code "46") (name "Net-(U200-PH1-OSC_OUT)") (class "Default")
      (node (ref "R200") (pin "2") (pinfunction "2_2") (pintype "passive"))
      (node (ref "U200") (pin "6") (pinfunction "PH1-OSC_OUT_6") (pintype "bidirectional"))
    )
    (net (code "47") (name "Net-(Y200-OSC2)") (class "Default")
      (node (ref "C201") (pin "2") (pinfunction "2_2") (pintype "passive"))
      (node (ref "R200") (pin "1") (pinfunction "1_1") (pintype "passive"))
      (node (ref "Y200") (pin "3") (pinfunction "OSC2_3") (pintype "passive"))
    )
    (net (code "48") (name "unconnected-(D201-Pad2)") (class "Default")
      (node (ref "D201") (pin "2") (pinfunction "2_2") (pintype "passive"))
    )
    (net (code "49") (name "unconnected-(J200-ID-Pad4)") (class "Default")
      (node (ref "J200") (pin "4") (pinfunction "ID_4") (pintype "passive+no_connect"))
    )
    (net (code "50") (name "unconnected-(J200-MNT_1-Pad6)") (class "Default")
      (node (ref "J200") (pin "6") (pinfunction "MNT_1_6") (pintype "passive+no_connect"))
    )
    (net (code "51") (name "unconnected-(J200-MNT_2-Pad7)") (class "Default")
      (node (ref "J200") (pin "7") (pinfunction "MNT_2_7") (pintype "passive+no_connect"))
    )
    (net (code "52") (name "unconnected-(J200-MNT_3-Pad8)") (class "Default")
      (node (ref "J200") (pin "8") (pinfunction "MNT_3_8") (pintype "passive+no_connect"))
    )
    (net (code "53") (name "unconnected-(J200-MNT_4-Pad9)") (class "Default")
      (node (ref "J200") (pin "9") (pinfunction "MNT_4_9") (pintype "passive+no_connect"))
    )
    (net (code "54") (name "unconnected-(J200-MNT_5-Pad10)") (class "Default")
      (node (ref "J200") (pin "10") (pinfunction "MNT_5_10") (pintype "passive+no_connect"))
    )
    (net (code "55") (name "unconnected-(J200-MNT_6-Pad11)") (class "Default")
      (node (ref "J200") (pin "11") (pinfunction "MNT_6_11") (pintype "passive+no_connect"))
    )
    (net (code "56") (name "unconnected-(J202-VSS-Pad6)") (class "Default")
      (node (ref "J202") (pin "6") (pinfunction "VSS_6") (pintype "power_in"))
    )
    (net (code "57") (name "unconnected-(J203-MNT_1-Pad7)") (class "Default")
      (node (ref "J203") (pin "7") (pinfunction "MNT_1_7") (pintype "passive"))
    )
    (net (code "58") (name "unconnected-(J203-MNT_2-Pad8)") (class "Default")
      (node (ref "J203") (pin "8") (pinfunction "MNT_2_8") (pintype "passive"))
    )
    (net (code "59") (name "unconnected-(R221-Pad1)") (class "Default")
      (node (ref "R221") (pin "1") (pinfunction "1_1") (pintype "passive"))
    )
    (net (code "60") (name "unconnected-(U200-PA0-WKUP-Pad10)") (class "Default")
      (node (ref "U200") (pin "10") (pinfunction "PA0-WKUP_10") (pintype "bidirectional+no_connect"))
    )
    (net (code "61") (name "unconnected-(U200-PA5-Pad15)") (class "Default")
      (node (ref "U200") (pin "15") (pinfunction "PA5_15") (pintype "bidirectional"))
    )
    (net (code "62") (name "unconnected-(U200-PA7-Pad17)") (class "Default")
      (node (ref "U200") (pin "17") (pinfunction "PA7_17") (pintype "bidirectional+no_connect"))
    )
    (net (code "63") (name "unconnected-(U200-PA10-Pad31)") (class "Default")
      (node (ref "U200") (pin "31") (pinfunction "PA10_31") (pintype "bidirectional+no_connect"))
    )
    (net (code "64") (name "unconnected-(U200-PA15-Pad38)") (class "Default")
      (node (ref "U200") (pin "38") (pinfunction "PA15_38") (pintype "bidirectional+no_connect"))
    )
    (net (code "65") (name "unconnected-(U200-PB0-Pad18)") (class "Default")
      (node (ref "U200") (pin "18") (pinfunction "PB0_18") (pintype "bidirectional+no_connect"))
    )
    (net (code "66") (name "unconnected-(U200-PB2-Pad20)") (class "Default")
      (node (ref "U200") (pin "20") (pinfunction "PB2_20") (pintype "bidirectional+no_connect"))
    )
    (net (code "67") (name "unconnected-(U200-PB14-Pad27)") (class "Default")
      (node (ref "U200") (pin "27") (pinfunction "PB14_27") (pintype "bidirectional+no_connect"))
    )
    (net (code "68") (name "unconnected-(U200-PC13-ANTI_TAMP-Pad2)") (class "Default")
      (node (ref "U200") (pin "2") (pinfunction "PC13-ANTI_TAMP_2") (pintype "bidirectional+no_connect"))
    )
    (net (code "69") (name "unconnected-(U200-PC14-OSC32_IN-Pad3)") (class "Default")
      (node (ref "U200") (pin "3") (pinfunction "PC14-OSC32_IN_3") (pintype "bidirectional+no_connect"))
    )
    (net (code "70") (name "unconnected-(U200-PC15-OSC32_OUT-Pad4)") (class "Default")
      (node (ref "U200") (pin "4") (pinfunction "PC15-OSC32_OUT_4") (pintype "bidirectional+no_connect"))
    )
  )
)
